# Rectifier.net
KiCad netlist of a schematic drawn in Altium Designer
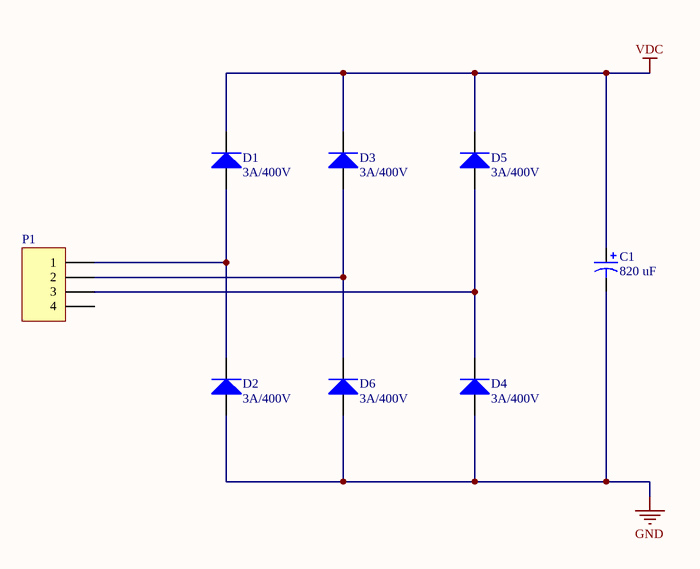
[diagram p0: Rectifier.SchDoc]

(export (version "E")
  (design (tool "Eeschema 10.0.6"))
  (components
    (comp (ref "C1")
      (value "820 uF")
      (footprint "ESMQ401VSN821MA45S")
      (description "CAP ALUM 820UF 20% 400V SNAP")
      (fields (field (name "Comment") "ESMQ401VSN821MA45S") (field (name "PUBLISHER") "Baris"))
      (libsource (lib "Viva") (part "ESMQ401VSN821MA45S"))
    )
    (comp (ref "D1")
      (value "3A/400V")
      (footprint "DO201AD")
      (description "DIODE GEN PURP 400V 3A DO201AD")
      (fields
        (field (name "MANUFACTURER") "DIODES INC.")
        (field (name "Comment") "DIODE GEN PURP 400V 3A DO201AD - 1N5404")
      )
      (libsource (lib "DISCRETE_LIB") (part "DIODE GEN PURP 400V 3A DO201AD - 1N5404"))
    )
    (comp (ref "D2")
      (value "3A/400V")
      (footprint "DO201AD")
      (description "DIODE GEN PURP 400V 3A DO201AD")
      (fields
        (field (name "MANUFACTURER") "DIODES INC.")
        (field (name "Comment") "DIODE GEN PURP 400V 3A DO201AD - 1N5404")
      )
      (libsource (lib "DISCRETE_LIB") (part "DIODE GEN PURP 400V 3A DO201AD - 1N5404"))
    )
    (comp (ref "D3")
      (value "3A/400V")
      (footprint "DO201AD")
      (description "DIODE GEN PURP 400V 3A DO201AD")
      (fields
        (field (name "MANUFACTURER") "DIODES INC.")
        (field (name "Comment") "DIODE GEN PURP 400V 3A DO201AD - 1N5404")
      )
      (libsource (lib "DISCRETE_LIB") (part "DIODE GEN PURP 400V 3A DO201AD - 1N5404"))
    )
    (comp (ref "D4")
      (value "3A/400V")
      (footprint "DO201AD")
      (description "DIODE GEN PURP 400V 3A DO201AD")
      (fields
        (field (name "MANUFACTURER") "DIODES INC.")
        (field (name "Comment") "DIODE GEN PURP 400V 3A DO201AD - 1N5404")
      )
      (libsource (lib "DISCRETE_LIB") (part "DIODE GEN PURP 400V 3A DO201AD - 1N5404"))
    )
    (comp (ref "D5")
      (value "3A/400V")
      (footprint "DO201AD")
      (description "DIODE GEN PURP 400V 3A DO201AD")
      (fields
        (field (name "MANUFACTURER") "DIODES INC.")
        (field (name "Comment") "DIODE GEN PURP 400V 3A DO201AD - 1N5404")
      )
      (libsource (lib "DISCRETE_LIB") (part "DIODE GEN PURP 400V 3A DO201AD - 1N5404"))
    )
    (comp (ref "D6")
      (value "3A/400V")
      (footprint "DO201AD")
      (description "DIODE GEN PURP 400V 3A DO201AD")
      (fields
        (field (name "MANUFACTURER") "DIODES INC.")
        (field (name "Comment") "DIODE GEN PURP 400V 3A DO201AD - 1N5404")
      )
      (libsource (lib "DISCRETE_LIB") (part "DIODE GEN PURP 400V 3A DO201AD - 1N5404"))
    )
    (comp (ref "P1")
      (value "CTB9358/4AO")
      (footprint "CTB9350/4AO")
      (description "4 pos plıggable terminal")
      (fields (field (name "PUBLISHER") "Sinan"))
      (libsource (lib "Viva") (part "CTB9358/4AO"))
    )
  )
  (nets
    (net (code "1") (name "GND") (class "Default")
      (node (ref "C1") (pin "2") (pinfunction "2_2") (pintype "passive"))
      (node (ref "D2") (pin "1") (pinfunction "A_1") (pintype "passive"))
      (node (ref "D4") (pin "1") (pinfunction "A_1") (pintype "passive"))
      (node (ref "D6") (pin "1") (pinfunction "A_1") (pintype "passive"))
    )
    (net (code "2") (name "Net-(D1-A)") (class "Default")
      (node (ref "D1") (pin "1") (pinfunction "A_1") (pintype "passive"))
      (node (ref "D2") (pin "2") (pinfunction "K_2") (pintype "passive"))
      (node (ref "P1") (pin "1") (pinfunction "1_1") (pintype "passive"))
    )
    (net (code "3") (name "Net-(D3-A)") (class "Default")
      (node (ref "D3") (pin "1") (pinfunction "A_1") (pintype "passive"))
      (node (ref "D6") (pin "2") (pinfunction "K_2") (pintype "passive"))
      (node (ref "P1") (pin "2") (pinfunction "2_2") (pintype "passive"))
    )
    (net (code "4") (name "Net-(D4-K)") (class "Default")
      (node (ref "D4") (pin "2") (pinfunction "K_2") (pintype "passive"))
      (node (ref "D5") (pin "1") (pinfunction "A_1") (pintype "passive"))
      (node (ref "P1") (pin "3") (pinfunction "3_3") (pintype "passive"))
    )
    (net (code "5") (name "VDC") (class "Default")
      (node (ref "C1") (pin "1") (pinfunction "1_1") (pintype "passive"))
      (node (ref "D1") (pin "2") (pinfunction "K_2") (pintype "passive"))
      (node (ref "D3") (pin "2") (pinfunction "K_2") (pintype "passive"))
      (node (ref "D5") (pin "2") (pinfunction "K_2") (pintype "passive"))
    )
    (net (code "6") (name "unconnected-(P1-Pad4)") (class "Default")
      (node (ref "P1") (pin "4") (pinfunction "4_4") (pintype "passive"))
    )
  )
)
